# MoxonCircuitBoard_v7.net
KiCad netlist of a schematic drawn in EAGLE
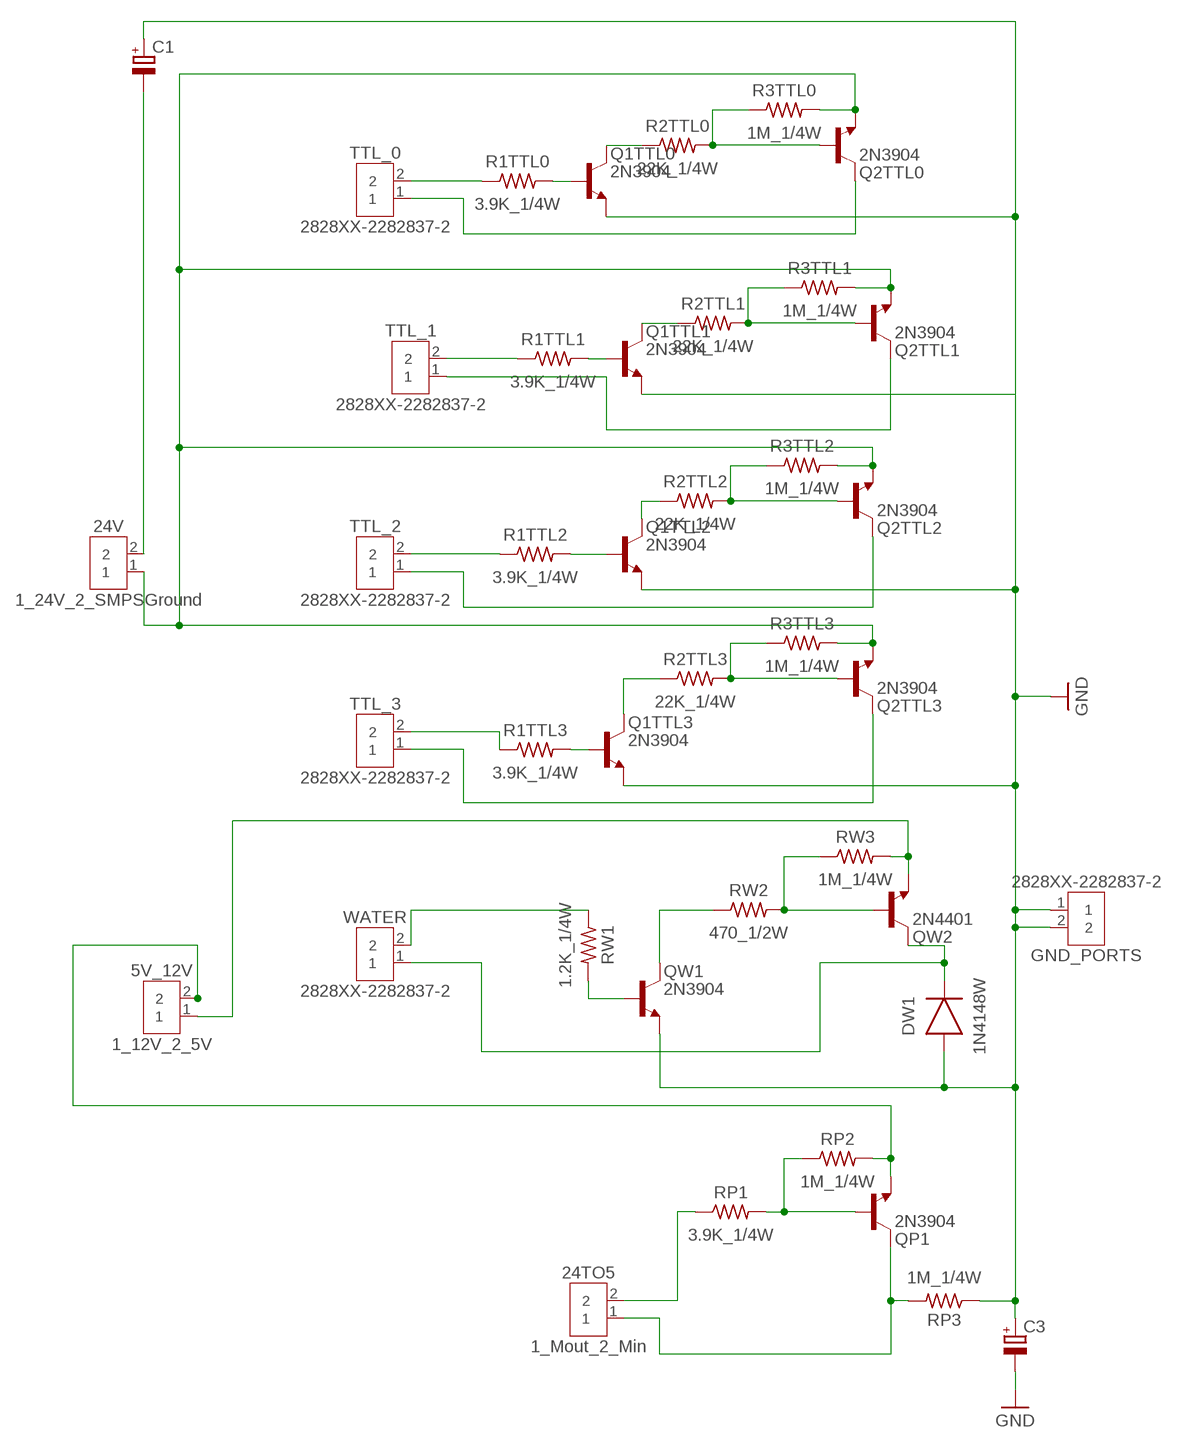
[diagram p0: schematic, sheet 1]

(export (version "E")
  (design (tool "Eeschema 10.0.6"))
  (components
    (comp (ref "5V_12V")
      (value "1_12V_2_5V")
      (footprint "eagle-import:TERMBLK_508-2N")
      (fields (field (name "MANUFACTURER") "TE Connectivity") (field (name "MPN") "282837-2"))
      (libsource (lib "eagle-import") (part "2828XX-2282837-2"))
    )
    (comp (ref "24TO5")
      (value "1_Mout_2_Min")
      (footprint "eagle-import:TERMBLK_508-2N")
      (fields (field (name "MANUFACTURER") "TE Connectivity") (field (name "MPN") "282837-2"))
      (libsource (lib "eagle-import") (part "2828XX-2282837-2"))
    )
    (comp (ref "24V")
      (value "1_24V_2_SMPSGround")
      (footprint "eagle-import:TERMBLK_508-2N")
      (fields (field (name "MANUFACTURER") "TE Connectivity") (field (name "MPN") "282837-2"))
      (libsource (lib "eagle-import") (part "2828XX-2282837-2"))
    )
    (comp (ref "C1")
      (value "C-POL_RADIAL-20MM-DIA")
      (footprint "eagle-import:CAPPRD550W60D1200H2000B")
      (libsource (lib "eagle-import") (part "C-POLRADIAL-20MM-DIA_"))
    )
    (comp (ref "C3")
      (value "C-POL_RADIAL-20MM-DIA")
      (footprint "eagle-import:CAPPRD550W60D1200H2000B")
      (libsource (lib "eagle-import") (part "C-POLRADIAL-20MM-DIA_"))
    )
    (comp (ref "DW1")
      (value "1N4148W")
      (footprint "eagle-import:SOD3715X135")
      (fields (field (name "MANUFACTURER") "Diodes Incorporated"))
      (libsource (lib "eagle-import") (part "DIODE__SOD123G1N4148W-7-F"))
    )
    (comp (ref "GND_PORTS")
      (value "2828XX-2282837-2")
      (footprint "eagle-import:TERMBLK_508-2N")
      (fields (field (name "MANUFACTURER") "TE Connectivity") (field (name "MPN") "282837-2"))
      (libsource (lib "eagle-import") (part "2828XX-2282837-2"))
    )
    (comp (ref "Q1TTL0")
      (value "2N3904")
      (footprint "eagle-import:TO92")
      (libsource (lib "eagle-import") (part "NPN__TO922N3904"))
    )
    (comp (ref "Q1TTL1")
      (value "2N3904")
      (footprint "eagle-import:TO92")
      (libsource (lib "eagle-import") (part "NPN__TO922N3904"))
    )
    (comp (ref "Q1TTL2")
      (value "2N3904")
      (footprint "eagle-import:TO92")
      (libsource (lib "eagle-import") (part "NPN__TO922N3904"))
    )
    (comp (ref "Q1TTL3")
      (value "2N3904")
      (footprint "eagle-import:TO92")
      (libsource (lib "eagle-import") (part "NPN__TO922N3904"))
    )
    (comp (ref "Q2TTL0")
      (value "2N3904")
      (footprint "eagle-import:TO92")
      (libsource (lib "eagle-import") (part "NPN__TO922N3904"))
    )
    (comp (ref "Q2TTL1")
      (value "2N3904")
      (footprint "eagle-import:TO92")
      (libsource (lib "eagle-import") (part "NPN__TO922N3904"))
    )
    (comp (ref "Q2TTL2")
      (value "2N3904")
      (footprint "eagle-import:TO92")
      (libsource (lib "eagle-import") (part "NPN__TO922N3904"))
    )
    (comp (ref "Q2TTL3")
      (value "2N3904")
      (footprint "eagle-import:TO92")
      (libsource (lib "eagle-import") (part "NPN__TO922N3904"))
    )
    (comp (ref "QP1")
      (value "2N3904")
      (footprint "eagle-import:TO92")
      (libsource (lib "eagle-import") (part "NPN__TO922N3904"))
    )
    (comp (ref "QW1")
      (value "2N3904")
      (footprint "eagle-import:TO92")
      (libsource (lib "eagle-import") (part "NPN__TO922N3904"))
    )
    (comp (ref "QW2")
      (value "2N4401")
      (footprint "eagle-import:TO92")
      (libsource (lib "eagle-import") (part "NPN__TO922N4401"))
    )
    (comp (ref "R1TTL0")
      (value "3.9K_1/4W")
      (footprint "eagle-import:RESAD1176W63L850D250B")
      (libsource (lib "eagle-import") (part "R-USAXIAL-11.7MM-PITCH_"))
    )
    (comp (ref "R1TTL1")
      (value "3.9K_1/4W")
      (footprint "eagle-import:RESAD1176W63L850D250B")
      (libsource (lib "eagle-import") (part "R-USAXIAL-11.7MM-PITCH_"))
    )
    (comp (ref "R1TTL2")
      (value "3.9K_1/4W")
      (footprint "eagle-import:RESAD1176W63L850D250B")
      (libsource (lib "eagle-import") (part "R-USAXIAL-11.7MM-PITCH_"))
    )
    (comp (ref "R1TTL3")
      (value "3.9K_1/4W")
      (footprint "eagle-import:RESAD1176W63L850D250B")
      (libsource (lib "eagle-import") (part "R-USAXIAL-11.7MM-PITCH_"))
    )
    (comp (ref "R2TTL0")
      (value "22K_1/4W")
      (footprint "eagle-import:RESAD1176W63L850D250B")
      (libsource (lib "eagle-import") (part "R-USAXIAL-11.7MM-PITCH_"))
    )
    (comp (ref "R2TTL1")
      (value "22K_1/4W")
      (footprint "eagle-import:RESAD1176W63L850D250B")
      (libsource (lib "eagle-import") (part "R-USAXIAL-11.7MM-PITCH_"))
    )
    (comp (ref "R2TTL2")
      (value "22K_1/4W")
      (footprint "eagle-import:RESAD1176W63L850D250B")
      (libsource (lib "eagle-import") (part "R-USAXIAL-11.7MM-PITCH_"))
    )
    (comp (ref "R2TTL3")
      (value "22K_1/4W")
      (footprint "eagle-import:RESAD1176W63L850D250B")
      (libsource (lib "eagle-import") (part "R-USAXIAL-11.7MM-PITCH_"))
    )
    (comp (ref "R3TTL0")
      (value "1M_1/4W")
      (footprint "eagle-import:RESAD1176W63L850D250B")
      (libsource (lib "eagle-import") (part "R-USAXIAL-11.7MM-PITCH_"))
    )
    (comp (ref "R3TTL1")
      (value "1M_1/4W")
      (footprint "eagle-import:RESAD1176W63L850D250B")
      (libsource (lib "eagle-import") (part "R-USAXIAL-11.7MM-PITCH_"))
    )
    (comp (ref "R3TTL2")
      (value "1M_1/4W")
      (footprint "eagle-import:RESAD1176W63L850D250B")
      (libsource (lib "eagle-import") (part "R-USAXIAL-11.7MM-PITCH_"))
    )
    (comp (ref "R3TTL3")
      (value "1M_1/4W")
      (footprint "eagle-import:RESAD1176W63L850D250B")
      (libsource (lib "eagle-import") (part "R-USAXIAL-11.7MM-PITCH_"))
    )
    (comp (ref "RP1")
      (value "3.9K_1/4W")
      (footprint "eagle-import:RESAD1176W63L850D250B")
      (libsource (lib "eagle-import") (part "R-USAXIAL-11.7MM-PITCH_"))
    )
    (comp (ref "RP2")
      (value "1M_1/4W")
      (footprint "eagle-import:RESAD1176W63L850D250B")
      (libsource (lib "eagle-import") (part "R-USAXIAL-11.7MM-PITCH_"))
    )
    (comp (ref "RP3")
      (value "1M_1/4W")
      (footprint "eagle-import:RESAD1176W63L850D250B")
      (libsource (lib "eagle-import") (part "R-USAXIAL-11.7MM-PITCH_"))
    )
    (comp (ref "RW1")
      (value "1.2K_1/4W")
      (footprint "eagle-import:RESAD1176W63L850D250B")
      (libsource (lib "eagle-import") (part "R-USAXIAL-11.7MM-PITCH_"))
    )
    (comp (ref "RW2")
      (value "470_1/2W")
      (footprint "eagle-import:RESAD1176W63L850D250B")
      (libsource (lib "eagle-import") (part "R-USAXIAL-11.7MM-PITCH_"))
    )
    (comp (ref "RW3")
      (value "1M_1/4W")
      (footprint "eagle-import:RESAD1176W63L850D250B")
      (libsource (lib "eagle-import") (part "R-USAXIAL-11.7MM-PITCH_"))
    )
    (comp (ref "TTL_0")
      (value "2828XX-2282837-2")
      (footprint "eagle-import:TERMBLK_508-2N")
      (fields (field (name "MANUFACTURER") "TE Connectivity") (field (name "MPN") "282837-2"))
      (libsource (lib "eagle-import") (part "2828XX-2282837-2"))
    )
    (comp (ref "TTL_1")
      (value "2828XX-2282837-2")
      (footprint "eagle-import:TERMBLK_508-2N")
      (fields (field (name "MANUFACTURER") "TE Connectivity") (field (name "MPN") "282837-2"))
      (libsource (lib "eagle-import") (part "2828XX-2282837-2"))
    )
    (comp (ref "TTL_2")
      (value "2828XX-2282837-2")
      (footprint "eagle-import:TERMBLK_508-2N")
      (fields (field (name "MANUFACTURER") "TE Connectivity") (field (name "MPN") "282837-2"))
      (libsource (lib "eagle-import") (part "2828XX-2282837-2"))
    )
    (comp (ref "TTL_3")
      (value "2828XX-2282837-2")
      (footprint "eagle-import:TERMBLK_508-2N")
      (fields (field (name "MANUFACTURER") "TE Connectivity") (field (name "MPN") "282837-2"))
      (libsource (lib "eagle-import") (part "2828XX-2282837-2"))
    )
    (comp (ref "WATER")
      (value "2828XX-2282837-2")
      (footprint "eagle-import:TERMBLK_508-2N")
      (fields (field (name "MANUFACTURER") "TE Connectivity") (field (name "MPN") "282837-2"))
      (libsource (lib "eagle-import") (part "2828XX-2282837-2"))
    )
  )
  (nets
    (net (code "1") (name "GND") (class "Default")
      (node (ref "C1") (pin "1") (pinfunction "+_1") (pintype "passive"))
      (node (ref "C3") (pin "1") (pinfunction "+_1") (pintype "passive"))
      (node (ref "C3") (pin "2") (pinfunction "-_2") (pintype "passive"))
      (node (ref "DW1") (pin "2") (pinfunction "A_2") (pintype "passive"))
      (node (ref "GND_PORTS") (pin "1") (pinfunction "1_1") (pintype "bidirectional"))
      (node (ref "GND_PORTS") (pin "2") (pinfunction "2_2") (pintype "bidirectional"))
      (node (ref "Q1TTL0") (pin "1") (pinfunction "E_1") (pintype "passive"))
      (node (ref "Q1TTL1") (pin "1") (pinfunction "E_1") (pintype "passive"))
      (node (ref "Q1TTL2") (pin "1") (pinfunction "E_1") (pintype "passive"))
      (node (ref "Q1TTL3") (pin "1") (pinfunction "E_1") (pintype "passive"))
      (node (ref "QW1") (pin "1") (pinfunction "E_1") (pintype "passive"))
      (node (ref "RP3") (pin "1") (pinfunction "1_1") (pintype "passive"))
    )
    (net (code "2") (name "Net-(24TO5-Pad2)") (class "Default")
      (node (ref "24TO5") (pin "2") (pinfunction "2_2") (pintype "bidirectional"))
      (node (ref "RP1") (pin "1") (pinfunction "1_1") (pintype "passive"))
    )
    (net (code "3") (name "Net-(C1--)") (class "Default")
      (node (ref "24V") (pin "2") (pinfunction "2_2") (pintype "bidirectional"))
      (node (ref "C1") (pin "2") (pinfunction "-_2") (pintype "passive"))
    )
    (net (code "4") (name "Net-(DW1-C)") (class "Default")
      (node (ref "DW1") (pin "1") (pinfunction "C_1") (pintype "passive"))
      (node (ref "QW2") (pin "3") (pinfunction "C_3") (pintype "passive"))
      (node (ref "WATER") (pin "1") (pinfunction "1_1") (pintype "bidirectional"))
    )
    (net (code "5") (name "Net-(Q1TTL0-B)") (class "Default")
      (node (ref "Q1TTL0") (pin "2") (pinfunction "B_2") (pintype "passive"))
      (node (ref "R1TTL0") (pin "2") (pinfunction "2_2") (pintype "passive"))
    )
    (net (code "6") (name "Net-(Q1TTL0-C)") (class "Default")
      (node (ref "Q1TTL0") (pin "3") (pinfunction "C_3") (pintype "passive"))
      (node (ref "R2TTL0") (pin "1") (pinfunction "1_1") (pintype "passive"))
    )
    (net (code "7") (name "Net-(Q1TTL1-B)") (class "Default")
      (node (ref "Q1TTL1") (pin "2") (pinfunction "B_2") (pintype "passive"))
      (node (ref "R1TTL1") (pin "2") (pinfunction "2_2") (pintype "passive"))
    )
    (net (code "8") (name "Net-(Q1TTL1-C)") (class "Default")
      (node (ref "Q1TTL1") (pin "3") (pinfunction "C_3") (pintype "passive"))
      (node (ref "R2TTL1") (pin "1") (pinfunction "1_1") (pintype "passive"))
    )
    (net (code "9") (name "Net-(Q1TTL2-B)") (class "Default")
      (node (ref "Q1TTL2") (pin "2") (pinfunction "B_2") (pintype "passive"))
      (node (ref "R1TTL2") (pin "2") (pinfunction "2_2") (pintype "passive"))
    )
    (net (code "10") (name "Net-(Q1TTL2-C)") (class "Default")
      (node (ref "Q1TTL2") (pin "3") (pinfunction "C_3") (pintype "passive"))
      (node (ref "R2TTL2") (pin "1") (pinfunction "1_1") (pintype "passive"))
    )
    (net (code "11") (name "Net-(Q1TTL3-B)") (class "Default")
      (node (ref "Q1TTL3") (pin "2") (pinfunction "B_2") (pintype "passive"))
      (node (ref "R1TTL3") (pin "2") (pinfunction "2_2") (pintype "passive"))
    )
    (net (code "12") (name "Net-(Q1TTL3-C)") (class "Default")
      (node (ref "Q1TTL3") (pin "3") (pinfunction "C_3") (pintype "passive"))
      (node (ref "R2TTL3") (pin "1") (pinfunction "1_1") (pintype "passive"))
    )
    (net (code "13") (name "Net-(Q2TTL0-B)") (class "Default")
      (node (ref "Q2TTL0") (pin "2") (pinfunction "B_2") (pintype "passive"))
      (node (ref "R2TTL0") (pin "2") (pinfunction "2_2") (pintype "passive"))
      (node (ref "R3TTL0") (pin "1") (pinfunction "1_1") (pintype "passive"))
    )
    (net (code "14") (name "Net-(Q2TTL0-C)") (class "Default")
      (node (ref "Q2TTL0") (pin "3") (pinfunction "C_3") (pintype "passive"))
      (node (ref "TTL_0") (pin "1") (pinfunction "1_1") (pintype "bidirectional"))
    )
    (net (code "15") (name "Net-(Q2TTL0-E)") (class "Default")
      (node (ref "24V") (pin "1") (pinfunction "1_1") (pintype "bidirectional"))
      (node (ref "Q2TTL0") (pin "1") (pinfunction "E_1") (pintype "passive"))
      (node (ref "Q2TTL1") (pin "1") (pinfunction "E_1") (pintype "passive"))
      (node (ref "Q2TTL2") (pin "1") (pinfunction "E_1") (pintype "passive"))
      (node (ref "Q2TTL3") (pin "1") (pinfunction "E_1") (pintype "passive"))
      (node (ref "R3TTL0") (pin "2") (pinfunction "2_2") (pintype "passive"))
      (node (ref "R3TTL1") (pin "2") (pinfunction "2_2") (pintype "passive"))
      (node (ref "R3TTL2") (pin "2") (pinfunction "2_2") (pintype "passive"))
      (node (ref "R3TTL3") (pin "2") (pinfunction "2_2") (pintype "passive"))
    )
    (net (code "16") (name "Net-(Q2TTL1-B)") (class "Default")
      (node (ref "Q2TTL1") (pin "2") (pinfunction "B_2") (pintype "passive"))
      (node (ref "R2TTL1") (pin "2") (pinfunction "2_2") (pintype "passive"))
      (node (ref "R3TTL1") (pin "1") (pinfunction "1_1") (pintype "passive"))
    )
    (net (code "17") (name "Net-(Q2TTL1-C)") (class "Default")
      (node (ref "Q2TTL1") (pin "3") (pinfunction "C_3") (pintype "passive"))
      (node (ref "TTL_1") (pin "1") (pinfunction "1_1") (pintype "bidirectional"))
    )
    (net (code "18") (name "Net-(Q2TTL2-B)") (class "Default")
      (node (ref "Q2TTL2") (pin "2") (pinfunction "B_2") (pintype "passive"))
      (node (ref "R2TTL2") (pin "2") (pinfunction "2_2") (pintype "passive"))
      (node (ref "R3TTL2") (pin "1") (pinfunction "1_1") (pintype "passive"))
    )
    (net (code "19") (name "Net-(Q2TTL2-C)") (class "Default")
      (node (ref "Q2TTL2") (pin "3") (pinfunction "C_3") (pintype "passive"))
      (node (ref "TTL_2") (pin "1") (pinfunction "1_1") (pintype "bidirectional"))
    )
    (net (code "20") (name "Net-(Q2TTL3-B)") (class "Default")
      (node (ref "Q2TTL3") (pin "2") (pinfunction "B_2") (pintype "passive"))
      (node (ref "R2TTL3") (pin "2") (pinfunction "2_2") (pintype "passive"))
      (node (ref "R3TTL3") (pin "1") (pinfunction "1_1") (pintype "passive"))
    )
    (net (code "21") (name "Net-(Q2TTL3-C)") (class "Default")
      (node (ref "Q2TTL3") (pin "3") (pinfunction "C_3") (pintype "passive"))
      (node (ref "TTL_3") (pin "1") (pinfunction "1_1") (pintype "bidirectional"))
    )
    (net (code "22") (name "Net-(QP1-B)") (class "Default")
      (node (ref "QP1") (pin "2") (pinfunction "B_2") (pintype "passive"))
      (node (ref "RP1") (pin "2") (pinfunction "2_2") (pintype "passive"))
      (node (ref "RP2") (pin "1") (pinfunction "1_1") (pintype "passive"))
    )
    (net (code "23") (name "Net-(QP1-C)") (class "Default")
      (node (ref "24TO5") (pin "1") (pinfunction "1_1") (pintype "bidirectional"))
      (node (ref "QP1") (pin "3") (pinfunction "C_3") (pintype "passive"))
      (node (ref "RP3") (pin "2") (pinfunction "2_2") (pintype "passive"))
    )
    (net (code "24") (name "Net-(QP1-E)") (class "Default")
      (node (ref "5V_12V") (pin "2") (pinfunction "2_2") (pintype "bidirectional"))
      (node (ref "QP1") (pin "1") (pinfunction "E_1") (pintype "passive"))
      (node (ref "RP2") (pin "2") (pinfunction "2_2") (pintype "passive"))
    )
    (net (code "25") (name "Net-(QW1-B)") (class "Default")
      (node (ref "QW1") (pin "2") (pinfunction "B_2") (pintype "passive"))
      (node (ref "RW1") (pin "2") (pinfunction "2_2") (pintype "passive"))
    )
    (net (code "26") (name "Net-(QW1-C)") (class "Default")
      (node (ref "QW1") (pin "3") (pinfunction "C_3") (pintype "passive"))
      (node (ref "RW2") (pin "1") (pinfunction "1_1") (pintype "passive"))
    )
    (net (code "27") (name "Net-(QW2-B)") (class "Default")
      (node (ref "QW2") (pin "2") (pinfunction "B_2") (pintype "passive"))
      (node (ref "RW2") (pin "2") (pinfunction "2_2") (pintype "passive"))
      (node (ref "RW3") (pin "1") (pinfunction "1_1") (pintype "passive"))
    )
    (net (code "28") (name "Net-(QW2-E)") (class "Default")
      (node (ref "5V_12V") (pin "1") (pinfunction "1_1") (pintype "bidirectional"))
      (node (ref "QW2") (pin "1") (pinfunction "E_1") (pintype "passive"))
      (node (ref "RW3") (pin "2") (pinfunction "2_2") (pintype "passive"))
    )
    (net (code "29") (name "Net-(R1TTL0-Pad1)") (class "Default")
      (node (ref "R1TTL0") (pin "1") (pinfunction "1_1") (pintype "passive"))
      (node (ref "TTL_0") (pin "2") (pinfunction "2_2") (pintype "bidirectional"))
    )
    (net (code "30") (name "Net-(R1TTL1-Pad1)") (class "Default")
      (node (ref "R1TTL1") (pin "1") (pinfunction "1_1") (pintype "passive"))
      (node (ref "TTL_1") (pin "2") (pinfunction "2_2") (pintype "bidirectional"))
    )
    (net (code "31") (name "Net-(R1TTL2-Pad1)") (class "Default")
      (node (ref "R1TTL2") (pin "1") (pinfunction "1_1") (pintype "passive"))
      (node (ref "TTL_2") (pin "2") (pinfunction "2_2") (pintype "bidirectional"))
    )
    (net (code "32") (name "Net-(R1TTL3-Pad1)") (class "Default")
      (node (ref "R1TTL3") (pin "1") (pinfunction "1_1") (pintype "passive"))
      (node (ref "TTL_3") (pin "2") (pinfunction "2_2") (pintype "bidirectional"))
    )
    (net (code "33") (name "Net-(RW1-Pad1)") (class "Default")
      (node (ref "RW1") (pin "1") (pinfunction "1_1") (pintype "passive"))
      (node (ref "WATER") (pin "2") (pinfunction "2_2") (pintype "bidirectional"))
    )
  )
)
